# KranControlV1_2.net
KiCad netlist of a schematic drawn in EAGLE
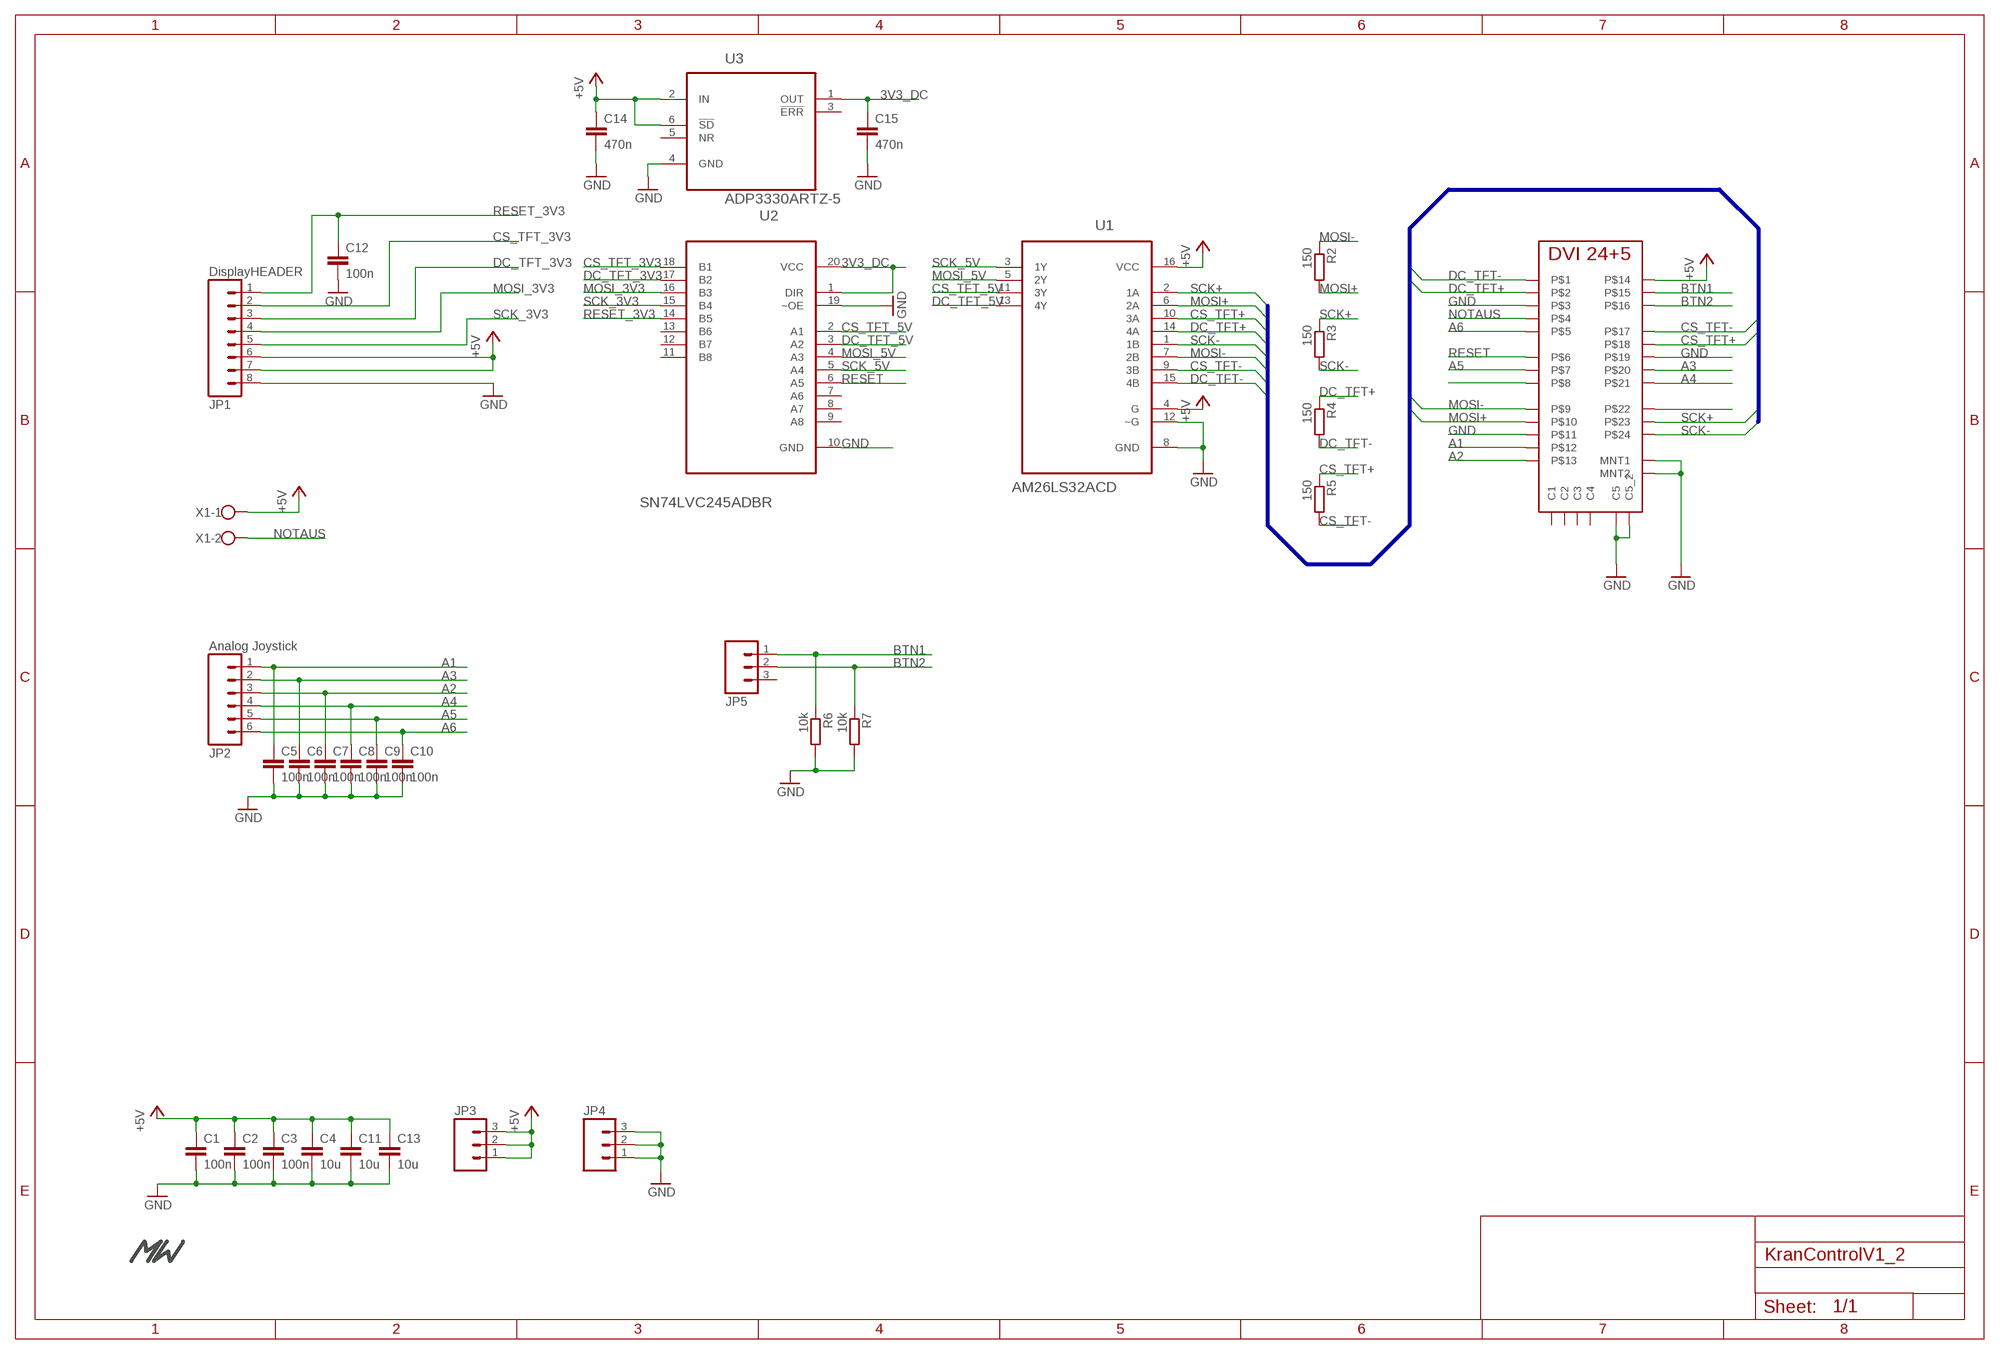
[diagram p0: schematic, sheet 1]

(export (version "E")
  (design (tool "Eeschema 10.0.6"))
  (components
    (comp (ref "C1")
      (value "100n")
      (footprint "eagle-import:C0603")
      (libsource (lib "eagle-import") (part "C-EUC0603"))
    )
    (comp (ref "C2")
      (value "100n")
      (footprint "eagle-import:C0603")
      (libsource (lib "eagle-import") (part "C-EUC0603"))
    )
    (comp (ref "C3")
      (value "100n")
      (footprint "eagle-import:C0603")
      (libsource (lib "eagle-import") (part "C-EUC0603"))
    )
    (comp (ref "C4")
      (value "10u")
      (footprint "eagle-import:C1206")
      (libsource (lib "eagle-import") (part "C-EUC1206"))
    )
    (comp (ref "C5")
      (value "100n")
      (footprint "eagle-import:C0603")
      (libsource (lib "eagle-import") (part "C-EUC0603"))
    )
    (comp (ref "C6")
      (value "100n")
      (footprint "eagle-import:C0603")
      (libsource (lib "eagle-import") (part "C-EUC0603"))
    )
    (comp (ref "C7")
      (value "100n")
      (footprint "eagle-import:C0603")
      (libsource (lib "eagle-import") (part "C-EUC0603"))
    )
    (comp (ref "C8")
      (value "100n")
      (footprint "eagle-import:C0603")
      (libsource (lib "eagle-import") (part "C-EUC0603"))
    )
    (comp (ref "C9")
      (value "100n")
      (footprint "eagle-import:C0603")
      (libsource (lib "eagle-import") (part "C-EUC0603"))
    )
    (comp (ref "C10")
      (value "100n")
      (footprint "eagle-import:C0603")
      (libsource (lib "eagle-import") (part "C-EUC0603"))
    )
    (comp (ref "C11")
      (value "10u")
      (footprint "eagle-import:C1206")
      (libsource (lib "eagle-import") (part "C-EUC1206"))
    )
    (comp (ref "C12")
      (value "100n")
      (footprint "eagle-import:C0603")
      (libsource (lib "eagle-import") (part "C-EUC0603"))
    )
    (comp (ref "C13")
      (value "10u")
      (footprint "eagle-import:C1206")
      (libsource (lib "eagle-import") (part "C-EUC1206"))
    )
    (comp (ref "C14")
      (value "470n")
      (footprint "eagle-import:C0603")
      (libsource (lib "eagle-import") (part "C-EUC0603"))
    )
    (comp (ref "C15")
      (value "470n")
      (footprint "eagle-import:C0603")
      (libsource (lib "eagle-import") (part "C-EUC0603"))
    )
    (comp (ref "JP1")
      (value "DisplayHEADER")
      (footprint "eagle-import:1X08_LOCK")
      (libsource (lib "eagle-import") (part "M08LOCK"))
    )
    (comp (ref "JP2")
      (value "Analog Joystick")
      (footprint "eagle-import:1X06_FEMALE_LOCK.010")
      (libsource (lib "eagle-import") (part "M06FEMALE_LOCK"))
    )
    (comp (ref "JP3")
      (value "M03LOCK")
      (footprint "eagle-import:1X03_LOCK")
      (libsource (lib "eagle-import") (part "M03LOCK"))
    )
    (comp (ref "JP4")
      (value "M03LOCK")
      (footprint "eagle-import:1X03_LOCK")
      (libsource (lib "eagle-import") (part "M03LOCK"))
    )
    (comp (ref "JP5")
      (value "M03LOCK")
      (footprint "eagle-import:1X03_LOCK")
      (libsource (lib "eagle-import") (part "M03LOCK"))
    )
    (comp (ref "R2")
      (value "150")
      (footprint "eagle-import:R0603")
      (libsource (lib "eagle-import") (part "R-EU_R0603"))
    )
    (comp (ref "R3")
      (value "150")
      (footprint "eagle-import:R0603")
      (libsource (lib "eagle-import") (part "R-EU_R0603"))
    )
    (comp (ref "R4")
      (value "150")
      (footprint "eagle-import:R0603")
      (libsource (lib "eagle-import") (part "R-EU_R0603"))
    )
    (comp (ref "R5")
      (value "150")
      (footprint "eagle-import:R0603")
      (libsource (lib "eagle-import") (part "R-EU_R0603"))
    )
    (comp (ref "R6")
      (value "10k")
      (footprint "eagle-import:R0603")
      (libsource (lib "eagle-import") (part "R-EU_R0603"))
    )
    (comp (ref "R7")
      (value "10k")
      (footprint "eagle-import:R0603")
      (libsource (lib "eagle-import") (part "R-EU_R0603"))
    )
    (comp (ref "U$1")
      (value "DVI_BUCHSE")
      (footprint "eagle-import:DVI_BUCHSE")
      (libsource (lib "eagle-import") (part "DVI_BUCHSE"))
    )
    (comp (ref "U$3")
      (value "MW_LOGO")
      (footprint "eagle-import:MW_11X5MM")
      (libsource (lib "eagle-import") (part "MW_LOGO"))
    )
    (comp (ref "U1")
      (value "AM26LS32ACD")
      (footprint "eagle-import:SOIC127P600X175-16N")
      (libsource (lib "eagle-import") (part "AM26LS32ACD"))
    )
    (comp (ref "U2")
      (value "SN74LVC245ADBR")
      (footprint "eagle-import:SOP65P780X200-20N")
      (libsource (lib "eagle-import") (part "SN74LVC245ADBR"))
    )
    (comp (ref "U3")
      (value "ADP3330ARTZ-5")
      (footprint "eagle-import:SOT95P280X145-6N")
      (libsource (lib "eagle-import") (part "ADP3330ARTZ-5"))
    )
    (comp (ref "X1")
      (value "W237-102")
      (footprint "eagle-import:W237-102")
      (fields (field (name "MPN") "237-102"))
      (libsource (lib "eagle-import") (part "W237-102"))
    )
  )
  (nets
    (net (code "1") (name "+5V") (class "Default")
      (node (ref "C1") (pin "1") (pinfunction "1_1") (pintype "passive"))
      (node (ref "C11") (pin "1") (pinfunction "1_1") (pintype "passive"))
      (node (ref "C13") (pin "1") (pinfunction "1_1") (pintype "passive"))
      (node (ref "C14") (pin "1") (pinfunction "1_1") (pintype "passive"))
      (node (ref "C2") (pin "1") (pinfunction "1_1") (pintype "passive"))
      (node (ref "C3") (pin "1") (pinfunction "1_1") (pintype "passive"))
      (node (ref "C4") (pin "1") (pinfunction "1_1") (pintype "passive"))
      (node (ref "JP1") (pin "6") (pinfunction "6_6") (pintype "passive"))
      (node (ref "JP1") (pin "7") (pinfunction "7_7") (pintype "passive"))
      (node (ref "JP3") (pin "1") (pinfunction "1_1") (pintype "passive"))
      (node (ref "JP3") (pin "2") (pinfunction "2_2") (pintype "passive"))
      (node (ref "JP3") (pin "3") (pinfunction "3_3") (pintype "passive"))
      (node (ref "U$1") (pin "P$14") (pinfunction "P$14_P$14") (pintype "bidirectional"))
      (node (ref "U1") (pin "16") (pinfunction "VCC_16") (pintype "power_in"))
      (node (ref "U1") (pin "4") (pinfunction "G_4") (pintype "input"))
      (node (ref "U3") (pin "2") (pinfunction "IN_2") (pintype "power_in"))
      (node (ref "U3") (pin "6") (pinfunction "~{SD}_6") (pintype "input"))
      (node (ref "X1") (pin "1") (pinfunction "KL_1") (pintype "passive"))
    )
    (net (code "2") (name "/3V3_DC") (class "Default")
      (node (ref "C15") (pin "1") (pinfunction "1_1") (pintype "passive"))
      (node (ref "U2") (pin "1") (pinfunction "DIR_1") (pintype "input"))
      (node (ref "U2") (pin "20") (pinfunction "VCC_20") (pintype "power_in"))
      (node (ref "U3") (pin "1") (pinfunction "OUT_1") (pintype "output"))
    )
    (net (code "3") (name "/A1") (class "Default")
      (node (ref "C5") (pin "1") (pinfunction "1_1") (pintype "passive"))
      (node (ref "JP2") (pin "1") (pinfunction "1_1") (pintype "passive"))
      (node (ref "U$1") (pin "P$12") (pinfunction "P$12_P$12") (pintype "bidirectional"))
    )
    (net (code "4") (name "/A2") (class "Default")
      (node (ref "C7") (pin "1") (pinfunction "1_1") (pintype "passive"))
      (node (ref "JP2") (pin "3") (pinfunction "3_3") (pintype "passive"))
      (node (ref "U$1") (pin "P$13") (pinfunction "P$13_P$13") (pintype "bidirectional"))
    )
    (net (code "5") (name "/A3") (class "Default")
      (node (ref "C6") (pin "1") (pinfunction "1_1") (pintype "passive"))
      (node (ref "JP2") (pin "2") (pinfunction "2_2") (pintype "passive"))
      (node (ref "U$1") (pin "P$4") (pinfunction "P$20_P$4") (pintype "bidirectional"))
    )
    (net (code "6") (name "/A4") (class "Default")
      (node (ref "C8") (pin "1") (pinfunction "1_1") (pintype "passive"))
      (node (ref "JP2") (pin "4") (pinfunction "4_4") (pintype "passive"))
      (node (ref "U$1") (pin "P$5") (pinfunction "P$21_P$5") (pintype "bidirectional"))
    )
    (net (code "7") (name "/A5") (class "Default")
      (node (ref "C9") (pin "1") (pinfunction "1_1") (pintype "passive"))
      (node (ref "JP2") (pin "5") (pinfunction "5_5") (pintype "passive"))
      (node (ref "U$1") (pin "P$23") (pinfunction "P$7_P$23") (pintype "bidirectional"))
    )
    (net (code "8") (name "/A6") (class "Default")
      (node (ref "C10") (pin "1") (pinfunction "1_1") (pintype "passive"))
      (node (ref "JP2") (pin "6") (pinfunction "6_6") (pintype "passive"))
      (node (ref "U$1") (pin "P$21") (pinfunction "P$5_P$21") (pintype "bidirectional"))
    )
    (net (code "9") (name "/BTN1") (class "Default")
      (node (ref "JP5") (pin "1") (pinfunction "1_1") (pintype "passive"))
      (node (ref "R6") (pin "1") (pinfunction "1_1") (pintype "passive"))
      (node (ref "U$1") (pin "P$15") (pinfunction "P$15_P$15") (pintype "bidirectional"))
    )
    (net (code "10") (name "/BTN2") (class "Default")
      (node (ref "JP5") (pin "2") (pinfunction "2_2") (pintype "passive"))
      (node (ref "R7") (pin "1") (pinfunction "1_1") (pintype "passive"))
      (node (ref "U$1") (pin "P$16") (pinfunction "P$16_P$16") (pintype "bidirectional"))
    )
    (net (code "11") (name "/CS_TFT+") (class "Default")
      (node (ref "R5") (pin "1") (pinfunction "1_1") (pintype "passive"))
      (node (ref "U$1") (pin "P$2") (pinfunction "P$18_P$2") (pintype "bidirectional"))
      (node (ref "U1") (pin "10") (pinfunction "3A_10") (pintype "input"))
    )
    (net (code "12") (name "/CS_TFT-") (class "Default")
      (node (ref "R5") (pin "2") (pinfunction "2_2") (pintype "passive"))
      (node (ref "U$1") (pin "P$1") (pinfunction "P$17_P$1") (pintype "bidirectional"))
      (node (ref "U1") (pin "9") (pinfunction "3B_9") (pintype "input"))
    )
    (net (code "13") (name "/CS_TFT_3V3") (class "Default")
      (node (ref "JP1") (pin "2") (pinfunction "2_2") (pintype "passive"))
      (node (ref "U2") (pin "18") (pinfunction "B1_18") (pintype "bidirectional"))
    )
    (net (code "14") (name "/CS_TFT_5V") (class "Default")
      (node (ref "U1") (pin "11") (pinfunction "3Y_11") (pintype "output"))
      (node (ref "U2") (pin "2") (pinfunction "A1_2") (pintype "bidirectional"))
    )
    (net (code "15") (name "/DC_TFT+") (class "Default")
      (node (ref "R4") (pin "1") (pinfunction "1_1") (pintype "passive"))
      (node (ref "U$1") (pin "P$18") (pinfunction "P$2_P$18") (pintype "bidirectional"))
      (node (ref "U1") (pin "14") (pinfunction "4A_14") (pintype "input"))
    )
    (net (code "16") (name "/DC_TFT-") (class "Default")
      (node (ref "R4") (pin "2") (pinfunction "2_2") (pintype "passive"))
      (node (ref "U$1") (pin "P$17") (pinfunction "P$1_P$17") (pintype "bidirectional"))
      (node (ref "U1") (pin "15") (pinfunction "4B_15") (pintype "input"))
    )
    (net (code "17") (name "/DC_TFT_3V3") (class "Default")
      (node (ref "JP1") (pin "3") (pinfunction "3_3") (pintype "passive"))
      (node (ref "U2") (pin "17") (pinfunction "B2_17") (pintype "bidirectional"))
    )
    (net (code "18") (name "/DC_TFT_5V") (class "Default")
      (node (ref "U1") (pin "13") (pinfunction "4Y_13") (pintype "output"))
      (node (ref "U2") (pin "3") (pinfunction "A2_3") (pintype "bidirectional"))
    )
    (net (code "19") (name "/MOSI+") (class "Default")
      (node (ref "R2") (pin "2") (pinfunction "2_2") (pintype "passive"))
      (node (ref "U$1") (pin "P$10") (pinfunction "P$10_P$10") (pintype "bidirectional"))
      (node (ref "U1") (pin "6") (pinfunction "2A_6") (pintype "input"))
    )
    (net (code "20") (name "/MOSI-") (class "Default")
      (node (ref "R2") (pin "1") (pinfunction "1_1") (pintype "passive"))
      (node (ref "U$1") (pin "P$9") (pinfunction "P$9_P$9") (pintype "bidirectional"))
      (node (ref "U1") (pin "7") (pinfunction "2B_7") (pintype "input"))
    )
    (net (code "21") (name "/MOSI_3V3") (class "Default")
      (node (ref "JP1") (pin "4") (pinfunction "4_4") (pintype "passive"))
      (node (ref "U2") (pin "16") (pinfunction "B3_16") (pintype "bidirectional"))
    )
    (net (code "22") (name "/MOSI_5V") (class "Default")
      (node (ref "U1") (pin "5") (pinfunction "2Y_5") (pintype "output"))
      (node (ref "U2") (pin "4") (pinfunction "A3_4") (pintype "bidirectional"))
    )
    (net (code "23") (name "/NOTAUS") (class "Default")
      (node (ref "U$1") (pin "P$20") (pinfunction "P$4_P$20") (pintype "bidirectional"))
      (node (ref "X1") (pin "2") (pinfunction "KL_2") (pintype "passive"))
    )
    (net (code "24") (name "/RESET") (class "Default")
      (node (ref "U$1") (pin "P$22") (pinfunction "P$6_P$22") (pintype "bidirectional"))
      (node (ref "U2") (pin "6") (pinfunction "A5_6") (pintype "bidirectional"))
    )
    (net (code "25") (name "/RESET_3V3") (class "Default")
      (node (ref "C12") (pin "1") (pinfunction "1_1") (pintype "passive"))
      (node (ref "JP1") (pin "1") (pinfunction "1_1") (pintype "passive"))
      (node (ref "U2") (pin "14") (pinfunction "B5_14") (pintype "bidirectional"))
    )
    (net (code "26") (name "/SCK+") (class "Default")
      (node (ref "R3") (pin "1") (pinfunction "1_1") (pintype "passive"))
      (node (ref "U$1") (pin "P$7") (pinfunction "P$23_P$7") (pintype "bidirectional"))
      (node (ref "U1") (pin "2") (pinfunction "1A_2") (pintype "input"))
    )
    (net (code "27") (name "/SCK-") (class "Default")
      (node (ref "R3") (pin "2") (pinfunction "2_2") (pintype "passive"))
      (node (ref "U$1") (pin "P$8") (pinfunction "P$24_P$8") (pintype "bidirectional"))
      (node (ref "U1") (pin "1") (pinfunction "1B_1") (pintype "input"))
    )
    (net (code "28") (name "/SCK_3V3") (class "Default")
      (node (ref "JP1") (pin "5") (pinfunction "5_5") (pintype "passive"))
      (node (ref "U2") (pin "15") (pinfunction "B4_15") (pintype "bidirectional"))
    )
    (net (code "29") (name "/SCK_5V") (class "Default")
      (node (ref "U1") (pin "3") (pinfunction "1Y_3") (pintype "output"))
      (node (ref "U2") (pin "5") (pinfunction "A4_5") (pintype "bidirectional"))
    )
    (net (code "30") (name "GND") (class "Default")
      (node (ref "C1") (pin "2") (pinfunction "2_2") (pintype "passive"))
      (node (ref "C10") (pin "2") (pinfunction "2_2") (pintype "passive"))
      (node (ref "C11") (pin "2") (pinfunction "2_2") (pintype "passive"))
      (node (ref "C12") (pin "2") (pinfunction "2_2") (pintype "passive"))
      (node (ref "C13") (pin "2") (pinfunction "2_2") (pintype "passive"))
      (node (ref "C14") (pin "2") (pinfunction "2_2") (pintype "passive"))
      (node (ref "C15") (pin "2") (pinfunction "2_2") (pintype "passive"))
      (node (ref "C2") (pin "2") (pinfunction "2_2") (pintype "passive"))
      (node (ref "C3") (pin "2") (pinfunction "2_2") (pintype "passive"))
      (node (ref "C4") (pin "2") (pinfunction "2_2") (pintype "passive"))
      (node (ref "C5") (pin "2") (pinfunction "2_2") (pintype "passive"))
      (node (ref "C6") (pin "2") (pinfunction "2_2") (pintype "passive"))
      (node (ref "C7") (pin "2") (pinfunction "2_2") (pintype "passive"))
      (node (ref "C8") (pin "2") (pinfunction "2_2") (pintype "passive"))
      (node (ref "C9") (pin "2") (pinfunction "2_2") (pintype "passive"))
      (node (ref "JP1") (pin "8") (pinfunction "8_8") (pintype "passive"))
      (node (ref "JP4") (pin "1") (pinfunction "1_1") (pintype "passive"))
      (node (ref "JP4") (pin "2") (pinfunction "2_2") (pintype "passive"))
      (node (ref "JP4") (pin "3") (pinfunction "3_3") (pintype "passive"))
      (node (ref "R6") (pin "2") (pinfunction "2_2") (pintype "passive"))
      (node (ref "R7") (pin "2") (pinfunction "2_2") (pintype "passive"))
      (node (ref "U$1") (pin "MNT1") (pinfunction "MNT1_MNT1") (pintype "bidirectional"))
      (node (ref "U$1") (pin "MNT2") (pinfunction "MNT2_MNT2") (pintype "bidirectional"))
      (node (ref "U$1") (pin "P$11") (pinfunction "P$11_P$11") (pintype "bidirectional"))
      (node (ref "U$1") (pin "P$19") (pinfunction "P$3_P$19") (pintype "bidirectional"))
      (node (ref "U$1") (pin "P$28") (pinfunction "C5_P$28") (pintype "bidirectional"))
      (node (ref "U$1") (pin "P$3") (pinfunction "P$19_P$3") (pintype "bidirectional"))
      (node (ref "U$1") (pin "P$30") (pinfunction "C5_2_P$30") (pintype "bidirectional"))
      (node (ref "U1") (pin "12") (pinfunction "~{G}_12") (pintype "input"))
      (node (ref "U1") (pin "8") (pinfunction "GND_8") (pintype "passive"))
      (node (ref "U2") (pin "10") (pinfunction "GND_10") (pintype "passive"))
      (node (ref "U2") (pin "19") (pinfunction "~{OE}_19") (pintype "bidirectional"))
      (node (ref "U3") (pin "4") (pinfunction "GND_4") (pintype "passive"))
    )
    (net (code "31") (name "unconnected-(JP5-Pad3)") (class "Default")
      (node (ref "JP5") (pin "3") (pinfunction "3_3") (pintype "passive"))
    )
    (net (code "32") (name "unconnected-(U$1-C1-PadP$29)") (class "Default")
      (node (ref "U$1") (pin "P$29") (pinfunction "C1_P$29") (pintype "bidirectional"))
    )
    (net (code "33") (name "unconnected-(U$1-C2-PadP$25)") (class "Default")
      (node (ref "U$1") (pin "P$25") (pinfunction "C2_P$25") (pintype "bidirectional"))
    )
    (net (code "34") (name "unconnected-(U$1-C3-PadP$27)") (class "Default")
      (node (ref "U$1") (pin "P$27") (pinfunction "C3_P$27") (pintype "bidirectional"))
    )
    (net (code "35") (name "unconnected-(U$1-C4-PadP$26)") (class "Default")
      (node (ref "U$1") (pin "P$26") (pinfunction "C4_P$26") (pintype "bidirectional"))
    )
    (net (code "36") (name "unconnected-(U$1-P$8-PadP$24)") (class "Default")
      (node (ref "U$1") (pin "P$24") (pinfunction "P$8_P$24") (pintype "bidirectional"))
    )
    (net (code "37") (name "unconnected-(U$1-P$22-PadP$6)") (class "Default")
      (node (ref "U$1") (pin "P$6") (pinfunction "P$22_P$6") (pintype "bidirectional"))
    )
    (net (code "38") (name "unconnected-(U2-A6-Pad7)") (class "Default")
      (node (ref "U2") (pin "7") (pinfunction "A6_7") (pintype "bidirectional"))
    )
    (net (code "39") (name "unconnected-(U2-A7-Pad8)") (class "Default")
      (node (ref "U2") (pin "8") (pinfunction "A7_8") (pintype "bidirectional"))
    )
    (net (code "40") (name "unconnected-(U2-A8-Pad9)") (class "Default")
      (node (ref "U2") (pin "9") (pinfunction "A8_9") (pintype "bidirectional"))
    )
    (net (code "41") (name "unconnected-(U2-B6-Pad13)") (class "Default")
      (node (ref "U2") (pin "13") (pinfunction "B6_13") (pintype "bidirectional"))
    )
    (net (code "42") (name "unconnected-(U2-B7-Pad12)") (class "Default")
      (node (ref "U2") (pin "12") (pinfunction "B7_12") (pintype "bidirectional"))
    )
    (net (code "43") (name "unconnected-(U2-B8-Pad11)") (class "Default")
      (node (ref "U2") (pin "11") (pinfunction "B8_11") (pintype "bidirectional"))
    )
    (net (code "44") (name "unconnected-(U3-NR-Pad5)") (class "Default")
      (node (ref "U3") (pin "5") (pinfunction "NR_5") (pintype "input"))
    )
    (net (code "45") (name "unconnected-(U3-~{ERR}-Pad3)") (class "Default")
      (node (ref "U3") (pin "3") (pinfunction "~{ERR}_3") (pintype "output"))
    )
  )
)
